# 5OR_1.net
KiCad netlist of a schematic drawn in EAGLE
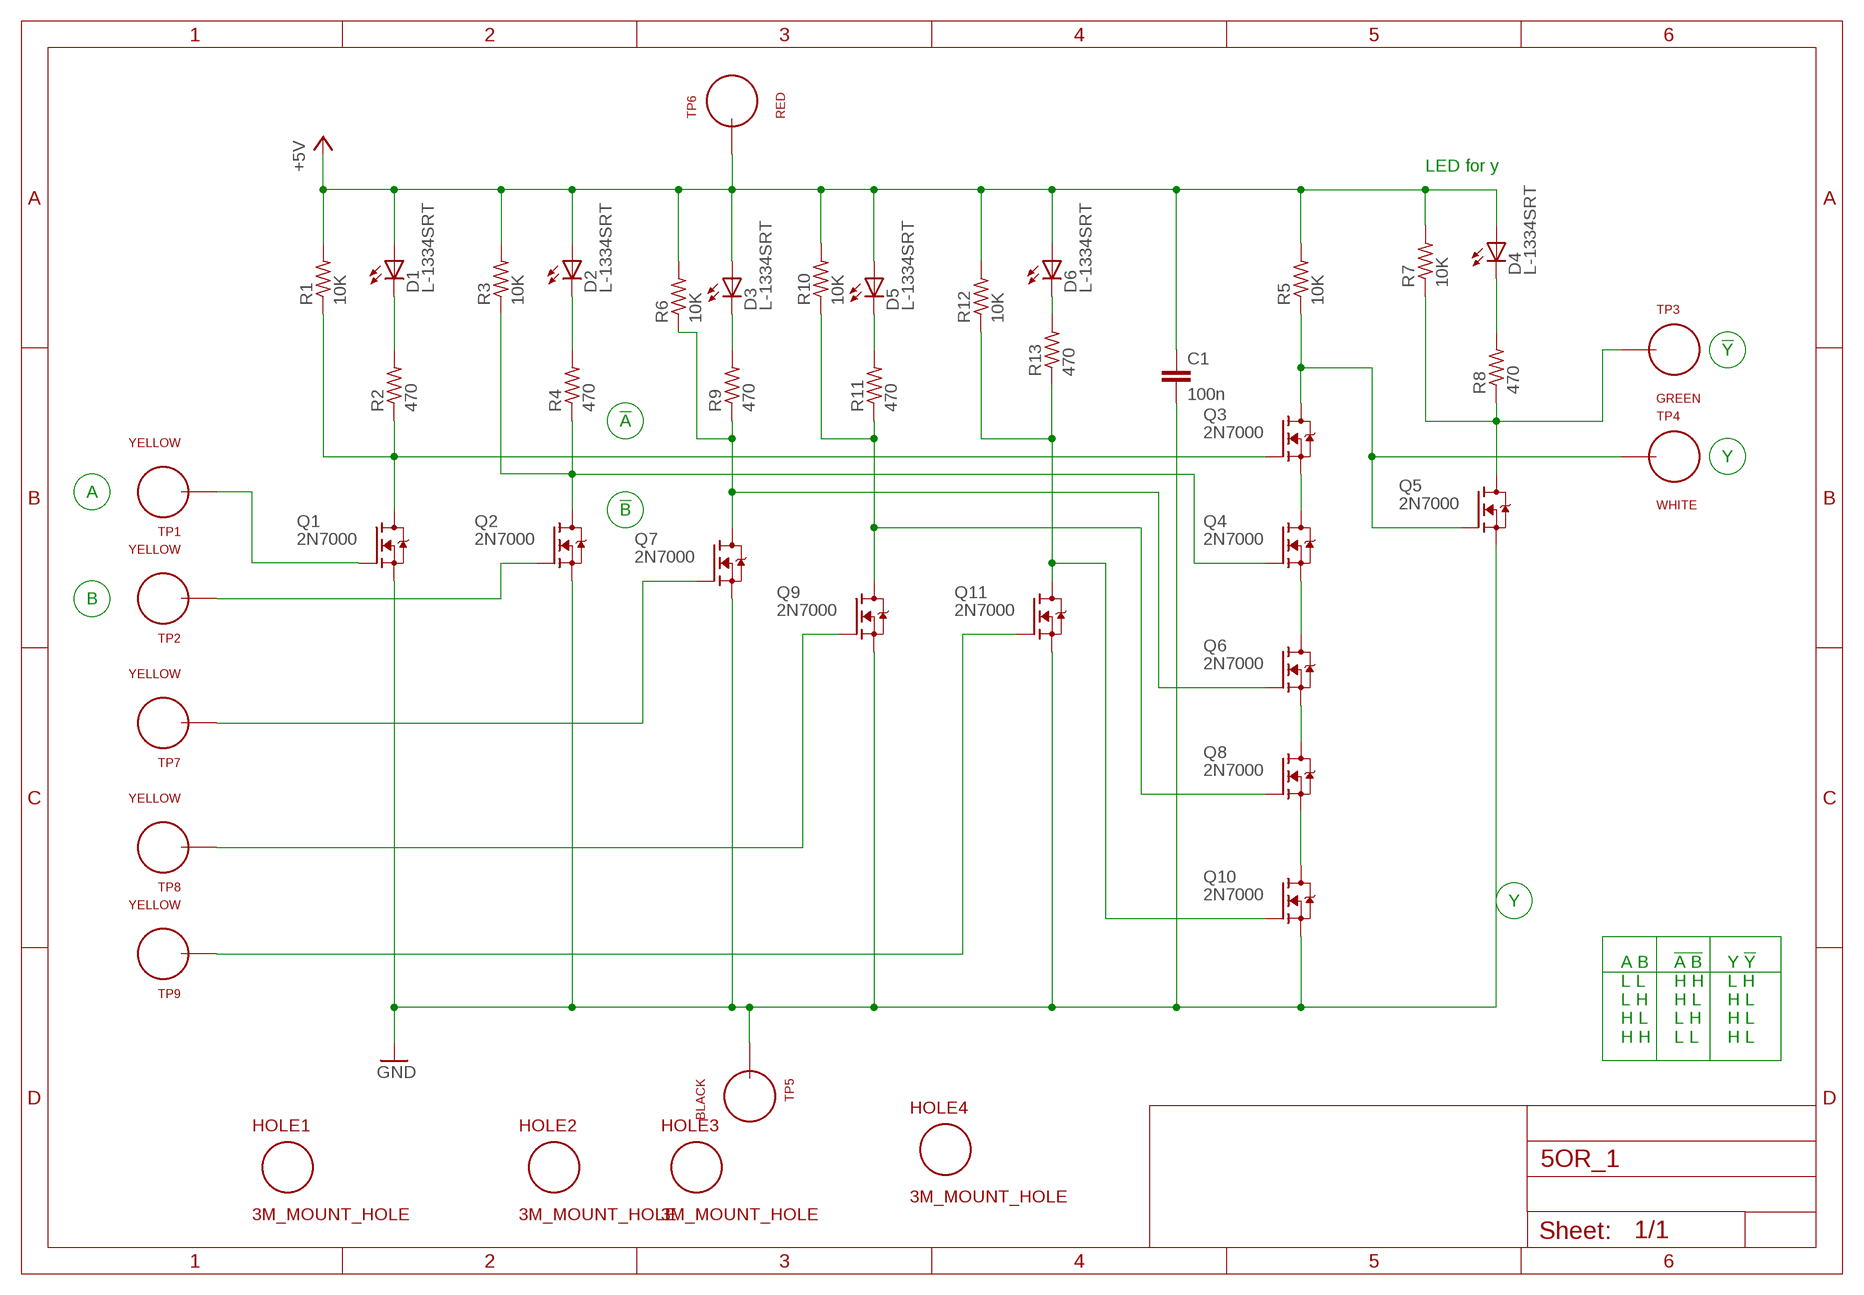
[diagram p0: schematic, sheet 1]

(export (version "E")
  (design (tool "Eeschema 10.0.6"))
  (components
    (comp (ref "C1")
      (value "100n")
      (footprint "eagle-import:CAP_P2INCH")
      (libsource (lib "eagle-import") (part "C_P2INCH"))
    )
    (comp (ref "D1")
      (value "L-1334SRT")
      (footprint "eagle-import:LED3MM")
      (libsource (lib "eagle-import") (part "L-1334SRT"))
    )
    (comp (ref "D2")
      (value "L-1334SRT")
      (footprint "eagle-import:LED3MM")
      (libsource (lib "eagle-import") (part "L-1334SRT"))
    )
    (comp (ref "D3")
      (value "L-1334SRT")
      (footprint "eagle-import:LED3MM")
      (libsource (lib "eagle-import") (part "L-1334SRT"))
    )
    (comp (ref "D4")
      (value "L-1334SRT")
      (footprint "eagle-import:LED3MM")
      (libsource (lib "eagle-import") (part "L-1334SRT"))
    )
    (comp (ref "D5")
      (value "L-1334SRT")
      (footprint "eagle-import:LED3MM")
      (libsource (lib "eagle-import") (part "L-1334SRT"))
    )
    (comp (ref "D6")
      (value "L-1334SRT")
      (footprint "eagle-import:LED3MM")
      (libsource (lib "eagle-import") (part "L-1334SRT"))
    )
    (comp (ref "HOLE1")
      (value "3M_MOUNT_HOLE")
      (footprint "eagle-import:3M_HOLE")
      (libsource (lib "eagle-import") (part "3M_MOUNT_HOLE"))
    )
    (comp (ref "HOLE2")
      (value "3M_MOUNT_HOLE")
      (footprint "eagle-import:3M_HOLE")
      (libsource (lib "eagle-import") (part "3M_MOUNT_HOLE"))
    )
    (comp (ref "HOLE3")
      (value "3M_MOUNT_HOLE")
      (footprint "eagle-import:3M_HOLE")
      (libsource (lib "eagle-import") (part "3M_MOUNT_HOLE"))
    )
    (comp (ref "HOLE4")
      (value "3M_MOUNT_HOLE")
      (footprint "eagle-import:3M_HOLE")
      (libsource (lib "eagle-import") (part "3M_MOUNT_HOLE"))
    )
    (comp (ref "Q1")
      (value "2N7000")
      (footprint "eagle-import:TO92-DGS")
      (libsource (lib "eagle-import") (part "2N7000"))
    )
    (comp (ref "Q2")
      (value "2N7000")
      (footprint "eagle-import:TO92-DGS")
      (libsource (lib "eagle-import") (part "2N7000"))
    )
    (comp (ref "Q3")
      (value "2N7000")
      (footprint "eagle-import:TO92-DGS")
      (libsource (lib "eagle-import") (part "2N7000"))
    )
    (comp (ref "Q4")
      (value "2N7000")
      (footprint "eagle-import:TO92-DGS")
      (libsource (lib "eagle-import") (part "2N7000"))
    )
    (comp (ref "Q5")
      (value "2N7000")
      (footprint "eagle-import:TO92-DGS")
      (libsource (lib "eagle-import") (part "2N7000"))
    )
    (comp (ref "Q6")
      (value "2N7000")
      (footprint "eagle-import:TO92-DGS")
      (libsource (lib "eagle-import") (part "2N7000"))
    )
    (comp (ref "Q7")
      (value "2N7000")
      (footprint "eagle-import:TO92-DGS")
      (libsource (lib "eagle-import") (part "2N7000"))
    )
    (comp (ref "Q8")
      (value "2N7000")
      (footprint "eagle-import:TO92-DGS")
      (libsource (lib "eagle-import") (part "2N7000"))
    )
    (comp (ref "Q9")
      (value "2N7000")
      (footprint "eagle-import:TO92-DGS")
      (libsource (lib "eagle-import") (part "2N7000"))
    )
    (comp (ref "Q10")
      (value "2N7000")
      (footprint "eagle-import:TO92-DGS")
      (libsource (lib "eagle-import") (part "2N7000"))
    )
    (comp (ref "Q11")
      (value "2N7000")
      (footprint "eagle-import:TO92-DGS")
      (libsource (lib "eagle-import") (part "2N7000"))
    )
    (comp (ref "R1")
      (value "10K")
      (footprint "eagle-import:R_P2INCH")
      (libsource (lib "eagle-import") (part "R_P2INCH"))
    )
    (comp (ref "R2")
      (value "470")
      (footprint "eagle-import:R_P2INCH")
      (libsource (lib "eagle-import") (part "R_P2INCH"))
    )
    (comp (ref "R3")
      (value "10K")
      (footprint "eagle-import:R_P2INCH")
      (libsource (lib "eagle-import") (part "R_P2INCH"))
    )
    (comp (ref "R4")
      (value "470")
      (footprint "eagle-import:R_P2INCH")
      (libsource (lib "eagle-import") (part "R_P2INCH"))
    )
    (comp (ref "R5")
      (value "10K")
      (footprint "eagle-import:R_P2INCH")
      (libsource (lib "eagle-import") (part "R_P2INCH"))
    )
    (comp (ref "R6")
      (value "10K")
      (footprint "eagle-import:R_P2INCH")
      (libsource (lib "eagle-import") (part "R_P2INCH"))
    )
    (comp (ref "R7")
      (value "10K")
      (footprint "eagle-import:R_P2INCH")
      (libsource (lib "eagle-import") (part "R_P2INCH"))
    )
    (comp (ref "R8")
      (value "470")
      (footprint "eagle-import:R_P2INCH")
      (libsource (lib "eagle-import") (part "R_P2INCH"))
    )
    (comp (ref "R9")
      (value "470")
      (footprint "eagle-import:R_P2INCH")
      (libsource (lib "eagle-import") (part "R_P2INCH"))
    )
    (comp (ref "R10")
      (value "10K")
      (footprint "eagle-import:R_P2INCH")
      (libsource (lib "eagle-import") (part "R_P2INCH"))
    )
    (comp (ref "R11")
      (value "470")
      (footprint "eagle-import:R_P2INCH")
      (libsource (lib "eagle-import") (part "R_P2INCH"))
    )
    (comp (ref "R12")
      (value "10K")
      (footprint "eagle-import:R_P2INCH")
      (libsource (lib "eagle-import") (part "R_P2INCH"))
    )
    (comp (ref "R13")
      (value "470")
      (footprint "eagle-import:R_P2INCH")
      (libsource (lib "eagle-import") (part "R_P2INCH"))
    )
    (comp (ref "TP1")
      (value "YELLOW")
      (footprint "eagle-import:TEST_LOOP")
      (libsource (lib "eagle-import") (part "TEST_LOOP"))
    )
    (comp (ref "TP2")
      (value "YELLOW")
      (footprint "eagle-import:TEST_LOOP")
      (libsource (lib "eagle-import") (part "TEST_LOOP"))
    )
    (comp (ref "TP3")
      (value "GREEN")
      (footprint "eagle-import:TEST_LOOP")
      (libsource (lib "eagle-import") (part "TEST_LOOP"))
    )
    (comp (ref "TP4")
      (value "WHITE")
      (footprint "eagle-import:TEST_LOOP")
      (libsource (lib "eagle-import") (part "TEST_LOOP"))
    )
    (comp (ref "TP5")
      (value "BLACK")
      (footprint "eagle-import:TEST_LOOP")
      (libsource (lib "eagle-import") (part "TEST_LOOP"))
    )
    (comp (ref "TP6")
      (value "RED")
      (footprint "eagle-import:TEST_LOOP")
      (libsource (lib "eagle-import") (part "TEST_LOOP"))
    )
    (comp (ref "TP7")
      (value "YELLOW")
      (footprint "eagle-import:TEST_LOOP")
      (libsource (lib "eagle-import") (part "TEST_LOOP"))
    )
    (comp (ref "TP8")
      (value "YELLOW")
      (footprint "eagle-import:TEST_LOOP")
      (libsource (lib "eagle-import") (part "TEST_LOOP"))
    )
    (comp (ref "TP9")
      (value "YELLOW")
      (footprint "eagle-import:TEST_LOOP")
      (libsource (lib "eagle-import") (part "TEST_LOOP"))
    )
  )
  (nets
    (net (code "1") (name "+5V") (class "Default")
      (node (ref "C1") (pin "1") (pinfunction "1_1") (pintype "passive"))
      (node (ref "D1") (pin "A") (pinfunction "A_A") (pintype "passive"))
      (node (ref "D2") (pin "A") (pinfunction "A_A") (pintype "passive"))
      (node (ref "D3") (pin "A") (pinfunction "A_A") (pintype "passive"))
      (node (ref "D4") (pin "A") (pinfunction "A_A") (pintype "passive"))
      (node (ref "D5") (pin "A") (pinfunction "A_A") (pintype "passive"))
      (node (ref "D6") (pin "A") (pinfunction "A_A") (pintype "passive"))
      (node (ref "R1") (pin "2") (pinfunction "2_2") (pintype "passive"))
      (node (ref "R10") (pin "2") (pinfunction "2_2") (pintype "passive"))
      (node (ref "R12") (pin "2") (pinfunction "2_2") (pintype "passive"))
      (node (ref "R3") (pin "2") (pinfunction "2_2") (pintype "passive"))
      (node (ref "R5") (pin "2") (pinfunction "2_2") (pintype "passive"))
      (node (ref "R6") (pin "2") (pinfunction "2_2") (pintype "passive"))
      (node (ref "R7") (pin "2") (pinfunction "2_2") (pintype "passive"))
      (node (ref "TP6") (pin "P$1") (pinfunction "P$1_P$1") (pintype "bidirectional"))
    )
    (net (code "2") (name "GND") (class "Default")
      (node (ref "C1") (pin "2") (pinfunction "2_2") (pintype "passive"))
      (node (ref "Q1") (pin "S") (pinfunction "S_S") (pintype "passive"))
      (node (ref "Q10") (pin "S") (pinfunction "S_S") (pintype "passive"))
      (node (ref "Q11") (pin "S") (pinfunction "S_S") (pintype "passive"))
      (node (ref "Q2") (pin "S") (pinfunction "S_S") (pintype "passive"))
      (node (ref "Q5") (pin "S") (pinfunction "S_S") (pintype "passive"))
      (node (ref "Q7") (pin "S") (pinfunction "S_S") (pintype "passive"))
      (node (ref "Q9") (pin "S") (pinfunction "S_S") (pintype "passive"))
      (node (ref "TP5") (pin "P$1") (pinfunction "P$1_P$1") (pintype "bidirectional"))
    )
    (net (code "3") (name "Net-(D1-C)") (class "Default")
      (node (ref "D1") (pin "K") (pinfunction "C_K") (pintype "passive"))
      (node (ref "R2") (pin "2") (pinfunction "2_2") (pintype "passive"))
    )
    (net (code "4") (name "Net-(D2-C)") (class "Default")
      (node (ref "D2") (pin "K") (pinfunction "C_K") (pintype "passive"))
      (node (ref "R4") (pin "2") (pinfunction "2_2") (pintype "passive"))
    )
    (net (code "5") (name "Net-(D3-C)") (class "Default")
      (node (ref "D3") (pin "K") (pinfunction "C_K") (pintype "passive"))
      (node (ref "R9") (pin "2") (pinfunction "2_2") (pintype "passive"))
    )
    (net (code "6") (name "Net-(D4-C)") (class "Default")
      (node (ref "D4") (pin "K") (pinfunction "C_K") (pintype "passive"))
      (node (ref "R8") (pin "2") (pinfunction "2_2") (pintype "passive"))
    )
    (net (code "7") (name "Net-(D5-C)") (class "Default")
      (node (ref "D5") (pin "K") (pinfunction "C_K") (pintype "passive"))
      (node (ref "R11") (pin "2") (pinfunction "2_2") (pintype "passive"))
    )
    (net (code "8") (name "Net-(D6-C)") (class "Default")
      (node (ref "D6") (pin "K") (pinfunction "C_K") (pintype "passive"))
      (node (ref "R13") (pin "2") (pinfunction "2_2") (pintype "passive"))
    )
    (net (code "9") (name "Net-(Q1-PadD)") (class "Default")
      (node (ref "Q1") (pin "D") (pinfunction "D_D") (pintype "passive"))
      (node (ref "Q3") (pin "G") (pinfunction "G_G") (pintype "passive"))
      (node (ref "R1") (pin "1") (pinfunction "1_1") (pintype "passive"))
      (node (ref "R2") (pin "1") (pinfunction "1_1") (pintype "passive"))
    )
    (net (code "10") (name "Net-(Q1-PadG)") (class "Default")
      (node (ref "Q1") (pin "G") (pinfunction "G_G") (pintype "passive"))
      (node (ref "TP1") (pin "P$1") (pinfunction "P$1_P$1") (pintype "bidirectional"))
    )
    (net (code "11") (name "Net-(Q2-PadD)") (class "Default")
      (node (ref "Q2") (pin "D") (pinfunction "D_D") (pintype "passive"))
      (node (ref "Q4") (pin "G") (pinfunction "G_G") (pintype "passive"))
      (node (ref "R3") (pin "1") (pinfunction "1_1") (pintype "passive"))
      (node (ref "R4") (pin "1") (pinfunction "1_1") (pintype "passive"))
    )
    (net (code "12") (name "Net-(Q2-PadG)") (class "Default")
      (node (ref "Q2") (pin "G") (pinfunction "G_G") (pintype "passive"))
      (node (ref "TP2") (pin "P$1") (pinfunction "P$1_P$1") (pintype "bidirectional"))
    )
    (net (code "13") (name "Net-(Q3-PadD)") (class "Default")
      (node (ref "Q3") (pin "D") (pinfunction "D_D") (pintype "passive"))
      (node (ref "Q5") (pin "G") (pinfunction "G_G") (pintype "passive"))
      (node (ref "R5") (pin "1") (pinfunction "1_1") (pintype "passive"))
      (node (ref "TP4") (pin "P$1") (pinfunction "P$1_P$1") (pintype "bidirectional"))
    )
    (net (code "14") (name "Net-(Q3-PadS)") (class "Default")
      (node (ref "Q3") (pin "S") (pinfunction "S_S") (pintype "passive"))
      (node (ref "Q4") (pin "D") (pinfunction "D_D") (pintype "passive"))
    )
    (net (code "15") (name "Net-(Q4-PadS)") (class "Default")
      (node (ref "Q4") (pin "S") (pinfunction "S_S") (pintype "passive"))
      (node (ref "Q6") (pin "D") (pinfunction "D_D") (pintype "passive"))
    )
    (net (code "16") (name "Net-(Q5-PadD)") (class "Default")
      (node (ref "Q5") (pin "D") (pinfunction "D_D") (pintype "passive"))
      (node (ref "R7") (pin "1") (pinfunction "1_1") (pintype "passive"))
      (node (ref "R8") (pin "1") (pinfunction "1_1") (pintype "passive"))
      (node (ref "TP3") (pin "P$1") (pinfunction "P$1_P$1") (pintype "bidirectional"))
    )
    (net (code "17") (name "Net-(Q6-PadG)") (class "Default")
      (node (ref "Q6") (pin "G") (pinfunction "G_G") (pintype "passive"))
      (node (ref "Q7") (pin "D") (pinfunction "D_D") (pintype "passive"))
      (node (ref "R6") (pin "1") (pinfunction "1_1") (pintype "passive"))
      (node (ref "R9") (pin "1") (pinfunction "1_1") (pintype "passive"))
    )
    (net (code "18") (name "Net-(Q6-PadS)") (class "Default")
      (node (ref "Q6") (pin "S") (pinfunction "S_S") (pintype "passive"))
      (node (ref "Q8") (pin "D") (pinfunction "D_D") (pintype "passive"))
    )
    (net (code "19") (name "Net-(Q7-PadG)") (class "Default")
      (node (ref "Q7") (pin "G") (pinfunction "G_G") (pintype "passive"))
      (node (ref "TP7") (pin "P$1") (pinfunction "P$1_P$1") (pintype "bidirectional"))
    )
    (net (code "20") (name "Net-(Q8-PadG)") (class "Default")
      (node (ref "Q8") (pin "G") (pinfunction "G_G") (pintype "passive"))
      (node (ref "Q9") (pin "D") (pinfunction "D_D") (pintype "passive"))
      (node (ref "R10") (pin "1") (pinfunction "1_1") (pintype "passive"))
      (node (ref "R11") (pin "1") (pinfunction "1_1") (pintype "passive"))
    )
    (net (code "21") (name "Net-(Q9-PadG)") (class "Default")
      (node (ref "Q9") (pin "G") (pinfunction "G_G") (pintype "passive"))
      (node (ref "TP8") (pin "P$1") (pinfunction "P$1_P$1") (pintype "bidirectional"))
    )
    (net (code "22") (name "Net-(Q10-PadD)") (class "Default")
      (node (ref "Q10") (pin "D") (pinfunction "D_D") (pintype "passive"))
      (node (ref "Q8") (pin "S") (pinfunction "S_S") (pintype "passive"))
    )
    (net (code "23") (name "Net-(Q10-PadG)") (class "Default")
      (node (ref "Q10") (pin "G") (pinfunction "G_G") (pintype "passive"))
      (node (ref "Q11") (pin "D") (pinfunction "D_D") (pintype "passive"))
      (node (ref "R12") (pin "1") (pinfunction "1_1") (pintype "passive"))
      (node (ref "R13") (pin "1") (pinfunction "1_1") (pintype "passive"))
    )
    (net (code "24") (name "Net-(Q11-PadG)") (class "Default")
      (node (ref "Q11") (pin "G") (pinfunction "G_G") (pintype "passive"))
      (node (ref "TP9") (pin "P$1") (pinfunction "P$1_P$1") (pintype "bidirectional"))
    )
  )
)
